# 13-ESP32C6.net
KiCad netlist of a schematic drawn in Altium Designer
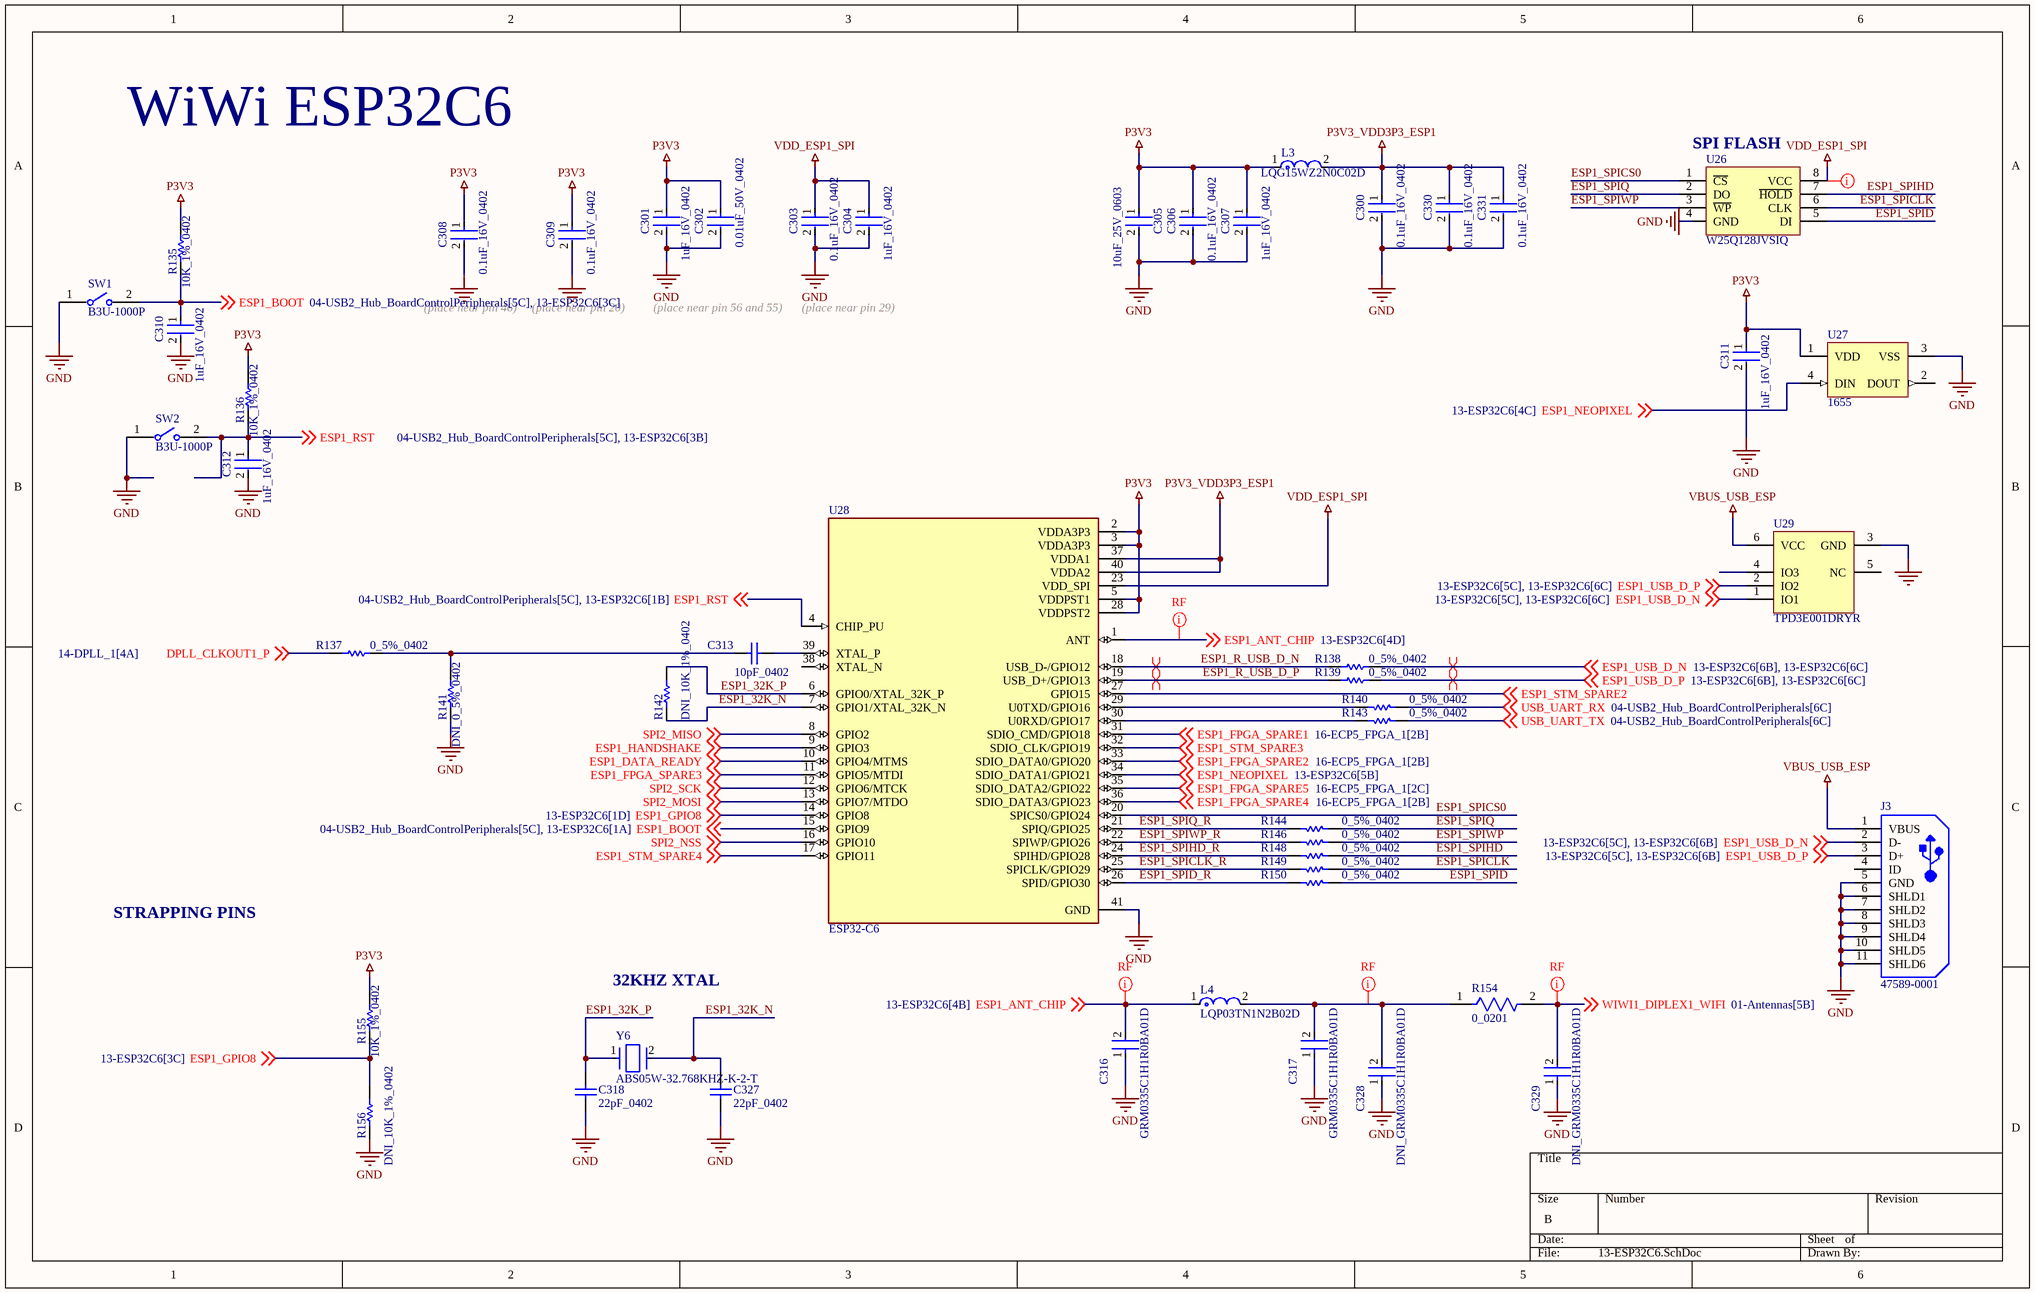
[diagram p0: 13-ESP32C6.SchDoc]

(export (version "E")
  (design (tool "Eeschema 10.0.6"))
  (components
    (comp (ref "C300")
      (value "0.1uF_16V_0402")
      (footprint "FP-C0402-BB-MFG")
      (description "CAP CER 0.1UF 16V 5% X7R 0402")
      (fields
        (field (name "MANUFACTURER") "Kemet")
        (field (name "MANUFACTURER PART NUMBER") "C0402C104J4RACTU")
      )
      (libsource (lib "Altium Content Vault") (part "b4654b650e69147ec39a6b967a45e02"))
    )
    (comp (ref "C301")
      (value "1uF_16V_0402")
      (footprint "FP-0402-L_1_0_0_05-W_0_5-IPC_A")
      (description "None")
      (fields (field (name "TOLERANCE") "10%"))
      (libsource (lib "Altium Content Vault") (part "b4654b650e69147ec39a6b967a45e02"))
    )
    (comp (ref "C302")
      (value "0.01uF_50V_0402")
      (footprint "FP-GCM155-0_05-IPC_C")
      (description "Ceramic Capacitor for Automotive 10nF ±10% 50VDC X7R 0402 Paper T/R")
      (fields (field (name "TOLERANCE") "10%") (field (name "VOLTAGE") "50V"))
      (libsource (lib "Altium Content Vault") (part "02cd4be3c70576c341d710602a673aa"))
    )
    (comp (ref "C303")
      (value "0.1uF_16V_0402")
      (footprint "FP-C0402-BB-MFG")
      (description "CAP CER 0.1UF 16V 5% X7R 0402")
      (fields
        (field (name "MANUFACTURER") "Kemet")
        (field (name "MANUFACTURER PART NUMBER") "C0402C104J4RACTU")
      )
      (libsource (lib "Altium Content Vault") (part "b4654b650e69147ec39a6b967a45e02"))
    )
    (comp (ref "C304")
      (value "1uF_16V_0402")
      (footprint "FP-0402-L_1_0_0_05-W_0_5-IPC_A")
      (description "None")
      (fields (field (name "TOLERANCE") "10%"))
      (libsource (lib "Altium Content Vault") (part "b4654b650e69147ec39a6b967a45e02"))
    )
    (comp (ref "C305")
      (value "10uF_25V_0603")
      (footprint "FP-CL10-IPC_C")
      (description "Cap Ceramic 10uF 25V X5R ±20% Pad SMD 0603 +85°C T/R")
      (fields (field (name "TOLERANCE") "20%"))
      (libsource (lib "Altium Content Vault") (part "b4654b650e69147ec39a6b967a45e02"))
    )
    (comp (ref "C306")
      (value "0.1uF_16V_0402")
      (footprint "FP-C0402-BB-MFG")
      (description "CAP CER 0.1UF 16V 5% X7R 0402")
      (fields
        (field (name "MANUFACTURER") "Kemet")
        (field (name "MANUFACTURER PART NUMBER") "C0402C104J4RACTU")
      )
      (libsource (lib "Altium Content Vault") (part "b4654b650e69147ec39a6b967a45e02"))
    )
    (comp (ref "C307")
      (value "1uF_16V_0402")
      (footprint "FP-0402-L_1_0_0_05-W_0_5-IPC_A")
      (description "None")
      (fields (field (name "TOLERANCE") "10%"))
      (libsource (lib "Altium Content Vault") (part "b4654b650e69147ec39a6b967a45e02"))
    )
    (comp (ref "C308")
      (value "0.1uF_16V_0402")
      (footprint "FP-C0402-BB-MFG")
      (description "CAP CER 0.1UF 16V 5% X7R 0402")
      (fields
        (field (name "MANUFACTURER") "Kemet")
        (field (name "MANUFACTURER PART NUMBER") "C0402C104J4RACTU")
      )
      (libsource (lib "Altium Content Vault") (part "b4654b650e69147ec39a6b967a45e02"))
    )
    (comp (ref "C309")
      (value "0.1uF_16V_0402")
      (footprint "FP-C0402-BB-MFG")
      (description "CAP CER 0.1UF 16V 5% X7R 0402")
      (fields
        (field (name "MANUFACTURER") "Kemet")
        (field (name "MANUFACTURER PART NUMBER") "C0402C104J4RACTU")
      )
      (libsource (lib "Altium Content Vault") (part "b4654b650e69147ec39a6b967a45e02"))
    )
    (comp (ref "C310")
      (value "1uF_16V_0402")
      (footprint "FP-0402-L_1_0_0_05-W_0_5-IPC_A")
      (description "None")
      (fields (field (name "TOLERANCE") "10%"))
      (libsource (lib "Altium Content Vault") (part "b4654b650e69147ec39a6b967a45e02"))
    )
    (comp (ref "C311")
      (value "1uF_16V_0402")
      (footprint "FP-0402-L_1_0_0_05-W_0_5-IPC_A")
      (description "None")
      (fields (field (name "TOLERANCE") "10%"))
      (libsource (lib "Altium Content Vault") (part "b4654b650e69147ec39a6b967a45e02"))
    )
    (comp (ref "C312")
      (value "1uF_16V_0402")
      (footprint "FP-0402-L_1_0_0_05-W_0_5-IPC_A")
      (description "None")
      (fields (field (name "TOLERANCE") "10%"))
      (libsource (lib "Altium Content Vault") (part "b4654b650e69147ec39a6b967a45e02"))
    )
    (comp (ref "C313")
      (value "10pF_0402")
      (footprint "CAPC1005X55X25ML05T05")
      (description "Chip Capacitor, 10 pF, +/- 5%, 50 V, -55 to 125 degC, 0402 (1005 Metric), RoHS, Tape and Reel")
      (fields (field (name "TOLERANCE") "5%") (field (name "MANUFACTURER") "Yageo"))
      (libsource (lib "Altium Content Vault") (part "CAP-NP-2"))
    )
    (comp (ref "C316")
      (value "GRM0335C1H1R0BA01D")
      (footprint "FP-GRM033-0_03-IPC_C")
      (description "Chip Multilayer Ceramic Capacitors for General Purpose, 0201, 1.0pF, C0G, 30ppm/°C, 0.1pF, 50V")
      (libsource (lib "Altium Content Vault") (part "b4654b650e69147ec39a6b967a45e02"))
    )
    (comp (ref "C317")
      (value "GRM0335C1H1R0BA01D")
      (footprint "FP-GRM033-0_03-IPC_C")
      (description "Chip Multilayer Ceramic Capacitors for General Purpose, 0201, 1.0pF, C0G, 30ppm/°C, 0.1pF, 50V")
      (libsource (lib "Altium Content Vault") (part "b4654b650e69147ec39a6b967a45e02"))
    )
    (comp (ref "C318")
      (value "22pF_0402")
      (footprint "CAPC1005X55X25ML05T05")
      (description "Chip Capacitor, 22 pF, +/- 5%, 50 V, -55 to 125 degC, 0402 (1005 Metric), RoHS, Tape and Reel")
      (fields (field (name "MANUFACTURER") "Yageo") (field (name "TOLERANCE") "5%"))
      (libsource (lib "Altium Content Vault") (part "CAP-NP-2"))
    )
    (comp (ref "C327")
      (value "22pF_0402")
      (footprint "CAPC1005X55X25ML05T05")
      (description "Chip Capacitor, 22 pF, +/- 5%, 50 V, -55 to 125 degC, 0402 (1005 Metric), RoHS, Tape and Reel")
      (fields (field (name "MANUFACTURER") "Yageo") (field (name "TOLERANCE") "5%"))
      (libsource (lib "Altium Content Vault") (part "CAP-NP-2"))
    )
    (comp (ref "C328")
      (value "DNI_GRM0335C1H1R0BA01D")
      (footprint "FP-GRM033-0_03-IPC_C")
      (description "Chip Multilayer Ceramic Capacitors for General Purpose, 0201, 1.0pF, C0G, 30ppm/°C, 0.1pF, 50V")
      (libsource (lib "Altium Content Vault") (part "b4654b650e69147ec39a6b967a45e02"))
    )
    (comp (ref "C329")
      (value "DNI_GRM0335C1H1R0BA01D")
      (footprint "FP-GRM033-0_03-IPC_C")
      (description "Chip Multilayer Ceramic Capacitors for General Purpose, 0201, 1.0pF, C0G, 30ppm/°C, 0.1pF, 50V")
      (libsource (lib "Altium Content Vault") (part "b4654b650e69147ec39a6b967a45e02"))
    )
    (comp (ref "C330")
      (value "0.1uF_16V_0402")
      (footprint "FP-C0402-BB-MFG")
      (description "CAP CER 0.1UF 16V 5% X7R 0402")
      (fields
        (field (name "MANUFACTURER") "Kemet")
        (field (name "MANUFACTURER PART NUMBER") "C0402C104J4RACTU")
      )
      (libsource (lib "Altium Content Vault") (part "b4654b650e69147ec39a6b967a45e02"))
    )
    (comp (ref "C331")
      (value "0.1uF_16V_0402")
      (footprint "FP-C0402-BB-MFG")
      (description "CAP CER 0.1UF 16V 5% X7R 0402")
      (fields
        (field (name "MANUFACTURER") "Kemet")
        (field (name "MANUFACTURER PART NUMBER") "C0402C104J4RACTU")
      )
      (libsource (lib "Altium Content Vault") (part "b4654b650e69147ec39a6b967a45e02"))
    )
    (comp (ref "J3")
      (value "47589-0001")
      (footprint "MOLX-47589-0001_V")
      (description "Right Angle Female Type AB Micro USB Connector, 30 V, 1.8 A, -30 to 85 degC, RoHS, Tape and Reel")
      (fields (field (name "MANUFACTURER") "Molex"))
      (libsource (lib "Altium Content Vault") (part "USB-5-6SHLD"))
    )
    (comp (ref "L3")
      (value "LQG15WZ2N0C02D")
      (footprint "FP-LQG15WH_02-IPC_B")
      (description "Multilayer type Inductor for Automotive 2nH ±0.2nH 0.05Ω 1000mA 0402")
      (libsource (lib "Altium Content Vault") (part "4cc4b267dca4c8e51f7102f422741d8"))
    )
    (comp (ref "L4")
      (value "LQP03TN1N2B02D")
      (footprint "FP-LQP03TG_02-IPC_A")
      (description "Film type RF Inductor 1.2nH ±0.1nH 750mA 0.1Ω 0201 (0603)")
      (libsource (lib "Altium Content Vault") (part "4cc4b267dca4c8e51f7102f422741d8"))
    )
    (comp (ref "R135")
      (value "10K_1%_0402")
      (footprint "RESC1005X40X25NL10T10")
      (fields (field (name "MANUFACTURER") "Bourns") (field (name "PART NUMBER") "CR0402-FX-1002GLF"))
      (libsource (lib "Altium Content Vault") (part "RES"))
    )
    (comp (ref "R136")
      (value "10K_1%_0402")
      (footprint "RESC1005X40X25NL10T10")
      (fields (field (name "MANUFACTURER") "Bourns") (field (name "PART NUMBER") "CR0402-FX-1002GLF"))
      (libsource (lib "Altium Content Vault") (part "RES"))
    )
    (comp (ref "R137")
      (value "0_5%_0402")
      (footprint "RESC1005X40X25NL05T10")
      (fields (field (name "MANUFACTURER") "Panasonic") (field (name "PART NUMBER") "ERJ-U020R00X"))
      (libsource (lib "Altium Content Vault") (part "RES"))
    )
    (comp (ref "R138")
      (value "0_5%_0402")
      (footprint "RESC1005X40X25NL05T10")
      (fields (field (name "MANUFACTURER") "Panasonic") (field (name "PART NUMBER") "ERJ-U020R00X"))
      (libsource (lib "Altium Content Vault") (part "RES"))
    )
    (comp (ref "R139")
      (value "0_5%_0402")
      (footprint "RESC1005X40X25NL05T10")
      (fields (field (name "MANUFACTURER") "Panasonic") (field (name "PART NUMBER") "ERJ-U020R00X"))
      (libsource (lib "Altium Content Vault") (part "RES"))
    )
    (comp (ref "R140")
      (value "0_5%_0402")
      (footprint "RESC1005X40X25NL05T10")
      (fields (field (name "MANUFACTURER") "Panasonic") (field (name "PART NUMBER") "ERJ-U020R00X"))
      (libsource (lib "Altium Content Vault") (part "RES"))
    )
    (comp (ref "R141")
      (value "DNI_0_5%_0402")
      (footprint "RESC1005X40X25NL05T10")
      (fields (field (name "MANUFACTURER") "Panasonic") (field (name "PART NUMBER") "ERJ-U020R00X"))
      (libsource (lib "Altium Content Vault") (part "RES"))
    )
    (comp (ref "R142")
      (value "DNI_10K_1%_0402")
      (footprint "RESC1005X40X25NL10T10")
      (fields (field (name "MANUFACTURER") "Bourns") (field (name "PART NUMBER") "CR0402-FX-1002GLF"))
      (libsource (lib "Altium Content Vault") (part "RES"))
    )
    (comp (ref "R143")
      (value "0_5%_0402")
      (footprint "RESC1005X40X25NL05T10")
      (fields (field (name "MANUFACTURER") "Panasonic") (field (name "PART NUMBER") "ERJ-U020R00X"))
      (libsource (lib "Altium Content Vault") (part "RES"))
    )
    (comp (ref "R144")
      (value "0_5%_0402")
      (footprint "RESC1005X40X25NL05T10")
      (fields (field (name "MANUFACTURER") "Panasonic") (field (name "PART NUMBER") "ERJ-U020R00X"))
      (libsource (lib "Altium Content Vault") (part "RES"))
    )
    (comp (ref "R146")
      (value "0_5%_0402")
      (footprint "RESC1005X40X25NL05T10")
      (fields (field (name "MANUFACTURER") "Panasonic") (field (name "PART NUMBER") "ERJ-U020R00X"))
      (libsource (lib "Altium Content Vault") (part "RES"))
    )
    (comp (ref "R148")
      (value "0_5%_0402")
      (footprint "RESC1005X40X25NL05T10")
      (fields (field (name "MANUFACTURER") "Panasonic") (field (name "PART NUMBER") "ERJ-U020R00X"))
      (libsource (lib "Altium Content Vault") (part "RES"))
    )
    (comp (ref "R149")
      (value "0_5%_0402")
      (footprint "RESC1005X40X25NL05T10")
      (fields (field (name "MANUFACTURER") "Panasonic") (field (name "PART NUMBER") "ERJ-U020R00X"))
      (libsource (lib "Altium Content Vault") (part "RES"))
    )
    (comp (ref "R150")
      (value "0_5%_0402")
      (footprint "RESC1005X40X25NL05T10")
      (fields (field (name "MANUFACTURER") "Panasonic") (field (name "PART NUMBER") "ERJ-U020R00X"))
      (libsource (lib "Altium Content Vault") (part "RES"))
    )
    (comp (ref "R154")
      (value "0_0201")
      (footprint "FP-RC_L0201-MFG")
      (description "RES SMD 0 OHM JUMPER 1/20W 0201")
      (fields
        (field (name "OCTOPART") "https://octopart.com/rc0201jr-070rl-yageo-43171986")
        (field (name "MANUFACTURER") "Yageo")
      )
      (libsource (lib "Altium Content Vault") (part "1029c3af85768c4190bb7ad29bc67b5"))
    )
    (comp (ref "R155")
      (value "10K_1%_0402")
      (footprint "RESC1005X40X25NL10T10")
      (fields (field (name "MANUFACTURER") "Bourns") (field (name "PART NUMBER") "CR0402-FX-1002GLF"))
      (libsource (lib "Altium Content Vault") (part "RES"))
    )
    (comp (ref "R156")
      (value "DNI_10K_1%_0402")
      (footprint "RESC1005X40X25NL10T10")
      (fields (field (name "MANUFACTURER") "Bourns") (field (name "PART NUMBER") "CR0402-FX-1002GLF"))
      (libsource (lib "Altium Content Vault") (part "RES"))
    )
    (comp (ref "SW1")
      (value "B3U-1000P")
      (footprint "FP-B3U-1000P-MFG")
      (description "SWITCH TACTILE SPST-NO 0.05A 12V")
      (libsource (lib "Altium Content Vault") (part "ae622034201233ca1abcedc05908f33"))
    )
    (comp (ref "SW2")
      (value "B3U-1000P")
      (footprint "FP-B3U-1000P-MFG")
      (description "SWITCH TACTILE SPST-NO 0.05A 12V")
      (libsource (lib "Altium Content Vault") (part "ae622034201233ca1abcedc05908f33"))
    )
    (comp (ref "U26")
      (value "W25Q128JVSIQ")
      (footprint "IC_W25Q128JVSIQ")
      (description "NOR Flash Serial (SPI, Dual SPI, Quad SPI) 3.3V 128M-bit 16M x 8 6ns 8-Pin SOIC Tube")
      (fields (field (name "MANUFACTURER") "Winbond"))
      (libsource (lib "LotusSound") (part "IC_W25Q128JVSIQ"))
    )
    (comp (ref "U27")
      (value "1655")
      (footprint "ADA-RGB-1655_V")
      (fields (field (name "MANUFACTURER") "Adafruit-Industries-LLC"))
      (libsource (lib "Altium Content Vault") (part "ADA-RGB-1655-4"))
    )
    (comp (ref "U28")
      (value "ESP32-C6")
      (footprint "QFN40P500X500X90-41N")
      (fields (field (name "MF") "Espressif Systems"))
      (libsource (lib "ESP32-C6") (part "ESP32-C6"))
    )
    (comp (ref "U29")
      (value "TPD3E001DRYR")
      (footprint "DRY0006A")
      (fields (field (name "MANUFACTURER") "Texas Instruments"))
      (libsource (lib "Altium Content Vault") (part "TI-TPD3E001-SON_DRY-6"))
    )
    (comp (ref "Y6")
      (value "ABS05W-32.768KHZ-K-2-T")
      (footprint "FP-ABS05W-MFG")
      (description "Crystal 32.768kHz ±20ppm (Tol) 4pF 85kΩ 2-Pin SMD T/R")
      (libsource (lib "Altium Content Vault") (part "c23a69dc6c9e2f18f2079038eb95dd1"))
    )
  )
  (nets
    (net (code "1") (name "/ESP1_32K_N") (class "Default")
      (node (ref "C327") (pin "2") (pinfunction "2_2") (pintype "passive"))
      (node (ref "R142") (pin "1") (pinfunction "1_1") (pintype "passive"))
      (node (ref "U28") (pin "7") (pinfunction "GPIO1/XTAL_32K_N_7") (pintype "bidirectional"))
      (node (ref "Y6") (pin "2") (pinfunction "2_2") (pintype "passive"))
    )
    (net (code "2") (name "/ESP1_32K_P") (class "Default")
      (node (ref "C318") (pin "2") (pinfunction "2_2") (pintype "passive"))
      (node (ref "R142") (pin "2") (pinfunction "2_2") (pintype "passive"))
      (node (ref "U28") (pin "6") (pinfunction "GPIO0/XTAL_32K_P_6") (pintype "bidirectional"))
      (node (ref "Y6") (pin "1") (pinfunction "1_1") (pintype "passive"))
    )
    (net (code "3") (name "/ESP1_R_USB_D_N") (class "Default")
      (node (ref "R138") (pin "1") (pinfunction "1_1") (pintype "passive"))
      (node (ref "U28") (pin "18") (pinfunction "USB_D-/GPIO12_18") (pintype "bidirectional"))
    )
    (net (code "4") (name "/ESP1_R_USB_D_P") (class "Default")
      (node (ref "R139") (pin "1") (pinfunction "1_1") (pintype "passive"))
      (node (ref "U28") (pin "19") (pinfunction "USB_D+/GPIO13_19") (pintype "bidirectional"))
    )
    (net (code "5") (name "/ESP1_SPICLK") (class "Default")
      (node (ref "R149") (pin "1") (pinfunction "1_1") (pintype "passive"))
      (node (ref "U26") (pin "6") (pinfunction "CLK_6") (pintype "passive"))
    )
    (net (code "6") (name "/ESP1_SPICLK_R") (class "Default")
      (node (ref "R149") (pin "2") (pinfunction "2_2") (pintype "passive"))
      (node (ref "U28") (pin "25") (pinfunction "SPICLK/GPIO29_25") (pintype "bidirectional"))
    )
    (net (code "7") (name "/ESP1_SPICS0") (class "Default")
      (node (ref "U26") (pin "1") (pinfunction "~{CS}_1") (pintype "passive"))
      (node (ref "U28") (pin "20") (pinfunction "SPICS0/GPIO24_20") (pintype "bidirectional"))
    )
    (net (code "8") (name "/ESP1_SPID") (class "Default")
      (node (ref "R150") (pin "1") (pinfunction "1_1") (pintype "passive"))
      (node (ref "U26") (pin "5") (pinfunction "DI_5") (pintype "passive"))
    )
    (net (code "9") (name "/ESP1_SPID_R") (class "Default")
      (node (ref "R150") (pin "2") (pinfunction "2_2") (pintype "passive"))
      (node (ref "U28") (pin "26") (pinfunction "SPID/GPIO30_26") (pintype "bidirectional"))
    )
    (net (code "10") (name "/ESP1_SPIHD") (class "Default")
      (node (ref "R148") (pin "1") (pinfunction "1_1") (pintype "passive"))
      (node (ref "U26") (pin "7") (pinfunction "~{HOLD}_7") (pintype "passive"))
    )
    (net (code "11") (name "/ESP1_SPIHD_R") (class "Default")
      (node (ref "R148") (pin "2") (pinfunction "2_2") (pintype "passive"))
      (node (ref "U28") (pin "24") (pinfunction "SPIHD/GPIO28_24") (pintype "bidirectional"))
    )
    (net (code "12") (name "/ESP1_SPIQ") (class "Default")
      (node (ref "R144") (pin "1") (pinfunction "1_1") (pintype "passive"))
      (node (ref "U26") (pin "2") (pinfunction "DO_2") (pintype "passive"))
    )
    (net (code "13") (name "/ESP1_SPIQ_R") (class "Default")
      (node (ref "R144") (pin "2") (pinfunction "2_2") (pintype "passive"))
      (node (ref "U28") (pin "21") (pinfunction "SPIQ/GPIO25_21") (pintype "bidirectional"))
    )
    (net (code "14") (name "/ESP1_SPIWP") (class "Default")
      (node (ref "R146") (pin "1") (pinfunction "1_1") (pintype "passive"))
      (node (ref "U26") (pin "3") (pinfunction "~{WP}_3") (pintype "passive"))
    )
    (net (code "15") (name "/ESP1_SPIWP_R") (class "Default")
      (node (ref "R146") (pin "2") (pinfunction "2_2") (pintype "passive"))
      (node (ref "U28") (pin "22") (pinfunction "SPIWP/GPIO26_22") (pintype "bidirectional"))
    )
    (net (code "16") (name "DPLL_CLKOUT1_P") (class "Default")
      (node (ref "R137") (pin "1") (pinfunction "1_1") (pintype "passive"))
    )
    (net (code "17") (name "ESP1_ANT_CHIP") (class "Default")
      (node (ref "C316") (pin "2") (pinfunction "2_2") (pintype "passive"))
      (node (ref "L4") (pin "1") (pinfunction "1_1") (pintype "passive"))
      (node (ref "U28") (pin "1") (pinfunction "ANT_1") (pintype "bidirectional"))
    )
    (net (code "18") (name "ESP1_BOOT") (class "Default")
      (node (ref "C310") (pin "1") (pinfunction "1_1") (pintype "passive"))
      (node (ref "R135") (pin "1") (pinfunction "1_1") (pintype "passive"))
      (node (ref "SW1") (pin "2") (pinfunction "2_2") (pintype "passive"))
      (node (ref "U28") (pin "15") (pinfunction "GPIO9_15") (pintype "bidirectional"))
    )
    (net (code "19") (name "ESP1_DATA_READY") (class "Default")
      (node (ref "U28") (pin "10") (pinfunction "GPIO4/MTMS_10") (pintype "bidirectional"))
    )
    (net (code "20") (name "ESP1_FPGA_SPARE1") (class "Default")
      (node (ref "U28") (pin "31") (pinfunction "SDIO_CMD/GPIO18_31") (pintype "bidirectional"))
    )
    (net (code "21") (name "ESP1_FPGA_SPARE2") (class "Default")
      (node (ref "U28") (pin "33") (pinfunction "SDIO_DATA0/GPIO20_33") (pintype "bidirectional"))
    )
    (net (code "22") (name "ESP1_FPGA_SPARE3") (class "Default")
      (node (ref "U28") (pin "11") (pinfunction "GPIO5/MTDI_11") (pintype "bidirectional"))
    )
    (net (code "23") (name "ESP1_FPGA_SPARE4") (class "Default")
      (node (ref "U28") (pin "36") (pinfunction "SDIO_DATA3/GPIO23_36") (pintype "bidirectional"))
    )
    (net (code "24") (name "ESP1_FPGA_SPARE5") (class "Default")
      (node (ref "U28") (pin "35") (pinfunction "SDIO_DATA2/GPIO22_35") (pintype "bidirectional"))
    )
    (net (code "25") (name "ESP1_GPIO8") (class "Default")
      (node (ref "R155") (pin "1") (pinfunction "1_1") (pintype "passive"))
      (node (ref "R156") (pin "2") (pinfunction "2_2") (pintype "passive"))
      (node (ref "U28") (pin "14") (pinfunction "GPIO8_14") (pintype "bidirectional"))
    )
    (net (code "26") (name "ESP1_HANDSHAKE") (class "Default")
      (node (ref "U28") (pin "9") (pinfunction "GPIO3_9") (pintype "bidirectional"))
    )
    (net (code "27") (name "ESP1_NEOPIXEL") (class "Default")
      (node (ref "U27") (pin "4") (pinfunction "DIN_4") (pintype "input"))
      (node (ref "U28") (pin "34") (pinfunction "SDIO_DATA1/GPIO21_34") (pintype "bidirectional"))
    )
    (net (code "28") (name "ESP1_RST") (class "Default")
      (node (ref "C312") (pin "1") (pinfunction "1_1") (pintype "passive"))
      (node (ref "R136") (pin "1") (pinfunction "1_1") (pintype "passive"))
      (node (ref "SW2") (pin "2") (pinfunction "2_2") (pintype "passive"))
      (node (ref "U28") (pin "4") (pinfunction "CHIP_PU_4") (pintype "input"))
    )
    (net (code "29") (name "ESP1_STM_SPARE2") (class "Default")
      (node (ref "U28") (pin "27") (pinfunction "GPIO15_27") (pintype "bidirectional"))
    )
    (net (code "30") (name "ESP1_STM_SPARE3") (class "Default")
      (node (ref "U28") (pin "32") (pinfunction "SDIO_CLK/GPIO19_32") (pintype "bidirectional"))
    )
    (net (code "31") (name "ESP1_STM_SPARE4") (class "Default")
      (node (ref "U28") (pin "17") (pinfunction "GPIO11_17") (pintype "bidirectional"))
    )
    (net (code "32") (name "ESP1_USB_D_N") (class "Default")
      (node (ref "J3") (pin "2") (pinfunction "D-_2") (pintype "passive"))
      (node (ref "R138") (pin "2") (pinfunction "2_2") (pintype "passive"))
      (node (ref "U29") (pin "1") (pinfunction "IO1_1") (pintype "passive"))
    )
    (net (code "33") (name "ESP1_USB_D_P") (class "Default")
      (node (ref "J3") (pin "3") (pinfunction "D+_3") (pintype "passive"))
      (node (ref "R139") (pin "2") (pinfunction "2_2") (pintype "passive"))
      (node (ref "U29") (pin "2") (pinfunction "IO2_2") (pintype "passive"))
    )
    (net (code "34") (name "GND") (class "Default")
      (node (ref "C300") (pin "2") (pinfunction "2_2") (pintype "passive"))
      (node (ref "C301") (pin "2") (pinfunction "2_2") (pintype "passive"))
      (node (ref "C302") (pin "2") (pinfunction "2_2") (pintype "passive"))
      (node (ref "C303") (pin "2") (pinfunction "2_2") (pintype "passive"))
      (node (ref "C304") (pin "2") (pinfunction "2_2") (pintype "passive"))
      (node (ref "C305") (pin "2") (pinfunction "2_2") (pintype "passive"))
      (node (ref "C306") (pin "2") (pinfunction "2_2") (pintype "passive"))
      (node (ref "C307") (pin "2") (pinfunction "2_2") (pintype "passive"))
      (node (ref "C308") (pin "2") (pinfunction "2_2") (pintype "passive"))
      (node (ref "C309") (pin "2") (pinfunction "2_2") (pintype "passive"))
      (node (ref "C310") (pin "2") (pinfunction "2_2") (pintype "passive"))
      (node (ref "C311") (pin "2") (pinfunction "2_2") (pintype "passive"))
      (node (ref "C312") (pin "2") (pinfunction "2_2") (pintype "passive"))
      (node (ref "C316") (pin "1") (pinfunction "1_1") (pintype "passive"))
      (node (ref "C317") (pin "1") (pinfunction "1_1") (pintype "passive"))
      (node (ref "C318") (pin "1") (pinfunction "1_1") (pintype "passive"))
      (node (ref "C327") (pin "1") (pinfunction "1_1") (pintype "passive"))
      (node (ref "C328") (pin "1") (pinfunction "1_1") (pintype "passive"))
      (node (ref "C329") (pin "1") (pinfunction "1_1") (pintype "passive"))
      (node (ref "C330") (pin "2") (pinfunction "2_2") (pintype "passive"))
      (node (ref "C331") (pin "2") (pinfunction "2_2") (pintype "passive"))
      (node (ref "J3") (pin "10") (pinfunction "SHLD5_10") (pintype "passive"))
      (node (ref "J3") (pin "11") (pinfunction "SHLD6_11") (pintype "passive"))
      (node (ref "J3") (pin "5") (pinfunction "GND_5") (pintype "passive"))
      (node (ref "J3") (pin "6") (pinfunction "SHLD1_6") (pintype "passive"))
      (node (ref "J3") (pin "7") (pinfunction "SHLD2_7") (pintype "passive"))
      (node (ref "J3") (pin "8") (pinfunction "SHLD3_8") (pintype "passive"))
      (node (ref "J3") (pin "9") (pinfunction "SHLD4_9") (pintype "passive"))
      (node (ref "R141") (pin "1") (pinfunction "1_1") (pintype "passive"))
      (node (ref "R156") (pin "1") (pinfunction "1_1") (pintype "passive"))
      (node (ref "SW1") (pin "1") (pinfunction "1_1") (pintype "passive"))
      (node (ref "SW2") (pin "1") (pinfunction "1_1") (pintype "passive"))
      (node (ref "U26") (pin "4") (pinfunction "GND_4") (pintype "power_in"))
      (node (ref "U27") (pin "3") (pinfunction "VSS_3") (pintype "power_in"))
      (node (ref "U28") (pin "41") (pinfunction "GND_41") (pintype "power_in"))
      (node (ref "U29") (pin "3") (pinfunction "GND_3") (pintype "power_in"))
    )
    (net (code "35") (name "Net-(C313-Pad1)") (class "Default")
      (node (ref "C313") (pin "1") (pinfunction "1_1") (pintype "passive"))
      (node (ref "R137") (pin "2") (pinfunction "2_2") (pintype "passive"))
      (node (ref "R141") (pin "2") (pinfunction "2_2") (pintype "passive"))
    )
    (net (code "36") (name "Net-(C317-Pad2)") (class "Default")
      (node (ref "C317") (pin "2") (pinfunction "2_2") (pintype "passive"))
      (node (ref "C328") (pin "2") (pinfunction "2_2") (pintype "passive"))
      (node (ref "L4") (pin "2") (pinfunction "2_2") (pintype "passive"))
      (node (ref "R154") (pin "1") (pinfunction "1_1") (pintype "passive"))
    )
    (net (code "37") (name "Net-(U28-U0RXD{slash}GPIO17)") (class "Default")
      (node (ref "R143") (pin "2") (pinfunction "2_2") (pintype "passive"))
      (node (ref "U28") (pin "30") (pinfunction "U0RXD/GPIO17_30") (pintype "bidirectional"))
    )
    (net (code "38") (name "Net-(U28-U0TXD{slash}GPIO16)") (class "Default")
      (node (ref "R140") (pin "2") (pinfunction "2_2") (pintype "passive"))
      (node (ref "U28") (pin "29") (pinfunction "U0TXD/GPIO16_29") (pintype "bidirectional"))
    )
    (net (code "39") (name "Net-(U28-XTAL_P)") (class "Default")
      (node (ref "C313") (pin "2") (pinfunction "2_2") (pintype "passive"))
      (node (ref "U28") (pin "39") (pinfunction "XTAL_P_39") (pintype "bidirectional"))
    )
    (net (code "40") (name "P3V3") (class "Default")
      (node (ref "C301") (pin "1") (pinfunction "1_1") (pintype "passive"))
      (node (ref "C302") (pin "1") (pinfunction "1_1") (pintype "passive"))
      (node (ref "C305") (pin "1") (pinfunction "1_1") (pintype "passive"))
      (node (ref "C306") (pin "1") (pinfunction "1_1") (pintype "passive"))
      (node (ref "C307") (pin "1") (pinfunction "1_1") (pintype "passive"))
      (node (ref "C308") (pin "1") (pinfunction "1_1") (pintype "passive"))
      (node (ref "C309") (pin "1") (pinfunction "1_1") (pintype "passive"))
      (node (ref "C311") (pin "1") (pinfunction "1_1") (pintype "passive"))
      (node (ref "L3") (pin "1") (pinfunction "1_1") (pintype "passive"))
      (node (ref "R135") (pin "2") (pinfunction "2_2") (pintype "passive"))
      (node (ref "R136") (pin "2") (pinfunction "2_2") (pintype "passive"))
      (node (ref "R155") (pin "2") (pinfunction "2_2") (pintype "passive"))
      (node (ref "U27") (pin "1") (pinfunction "VDD_1") (pintype "power_in"))
      (node (ref "U28") (pin "2") (pinfunction "VDDA3P3_2") (pintype "power_in"))
      (node (ref "U28") (pin "28") (pinfunction "VDDPST2_28") (pintype "power_in"))
      (node (ref "U28") (pin "3") (pinfunction "VDDA3P3_3") (pintype "power_in"))
      (node (ref "U28") (pin "5") (pinfunction "VDDPST1_5") (pintype "power_in"))
    )
    (net (code "41") (name "P3V3_VDD3P3_ESP1") (class "Default")
      (node (ref "C300") (pin "1") (pinfunction "1_1") (pintype "passive"))
      (node (ref "C330") (pin "1") (pinfunction "1_1") (pintype "passive"))
      (node (ref "C331") (pin "1") (pinfunction "1_1") (pintype "passive"))
      (node (ref "L3") (pin "2") (pinfunction "2_2") (pintype "passive"))
      (node (ref "U28") (pin "37") (pinfunction "VDDA1_37") (pintype "power_in"))
      (node (ref "U28") (pin "40") (pinfunction "VDDA2_40") (pintype "power_in"))
    )
    (net (code "42") (name "SPI2_MISO") (class "Default")
      (node (ref "U28") (pin "8") (pinfunction "GPIO2_8") (pintype "bidirectional"))
    )
    (net (code "43") (name "SPI2_MOSI") (class "Default")
      (node (ref "U28") (pin "13") (pinfunction "GPIO7/MTDO_13") (pintype "bidirectional"))
    )
    (net (code "44") (name "SPI2_NSS") (class "Default")
      (node (ref "U28") (pin "16") (pinfunction "GPIO10_16") (pintype "bidirectional"))
    )
    (net (code "45") (name "SPI2_SCK") (class "Default")
      (node (ref "U28") (pin "12") (pinfunction "GPIO6/MTCK_12") (pintype "bidirectional"))
    )
    (net (code "46") (name "USB_UART_RX") (class "Default")
      (node (ref "R140") (pin "1") (pinfunction "1_1") (pintype "passive"))
    )
    (net (code "47") (name "USB_UART_TX") (class "Default")
      (node (ref "R143") (pin "1") (pinfunction "1_1") (pintype "passive"))
    )
    (net (code "48") (name "VBUS_USB_ESP") (class "Default")
      (node (ref "J3") (pin "1") (pinfunction "VBUS_1") (pintype "passive"))
      (node (ref "U29") (pin "6") (pinfunction "VCC_6") (pintype "power_in"))
    )
    (net (code "49") (name "VDD_ESP1_SPI") (class "Default")
      (node (ref "C303") (pin "1") (pinfunction "1_1") (pintype "passive"))
      (node (ref "C304") (pin "1") (pinfunction "1_1") (pintype "passive"))
      (node (ref "U26") (pin "8") (pinfunction "VCC_8") (pintype "passive"))
      (node (ref "U28") (pin "23") (pinfunction "VDD_SPI_23") (pintype "power_in"))
    )
    (net (code "50") (name "WIWI1_DIPLEX1_WIFI") (class "Default")
      (node (ref "C329") (pin "2") (pinfunction "2_2") (pintype "passive"))
      (node (ref "R154") (pin "2") (pinfunction "2_2") (pintype "passive"))
    )
    (net (code "51") (name "unconnected-(J3-ID-Pad4)") (class "Default")
      (node (ref "J3") (pin "4") (pinfunction "ID_4") (pintype "passive"))
    )
    (net (code "52") (name "unconnected-(U27-DOUT-Pad2)") (class "Default")
      (node (ref "U27") (pin "2") (pinfunction "DOUT_2") (pintype "output"))
    )
    (net (code "53") (name "unconnected-(U28-XTAL_N-Pad38)") (class "Default")
      (node (ref "U28") (pin "38") (pinfunction "XTAL_N_38") (pintype "bidirectional"))
    )
    (net (code "54") (name "unconnected-(U29-IO3-Pad4)") (class "Default")
      (node (ref "U29") (pin "4") (pinfunction "IO3_4") (pintype "passive"))
    )
    (net (code "55") (name "unconnected-(U29-NC-Pad5)") (class "Default")
      (node (ref "U29") (pin "5") (pinfunction "NC_5") (pintype "passive"))
    )
  )
)
